# USB_OTG_FS.net
KiCad netlist of a schematic drawn in Altium Designer
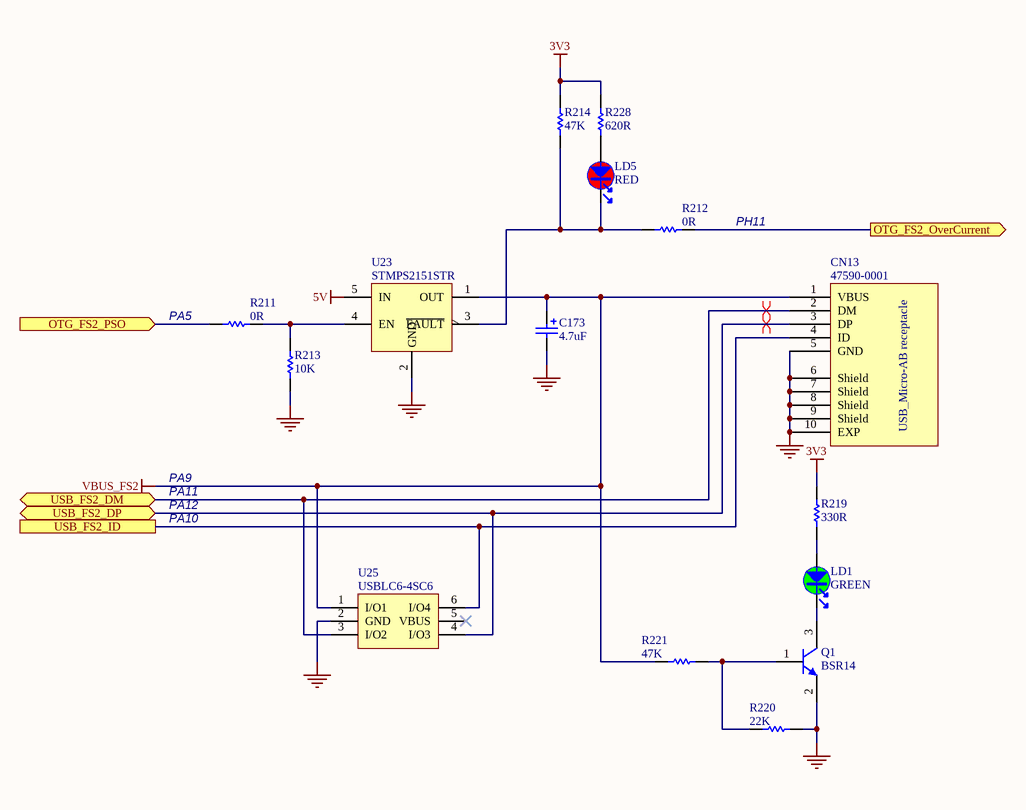
[diagram p0: USB_OTG_FS.SchDoc]

(export (version "E")
  (design (tool "Eeschema 10.0.6"))
  (components
    (comp (ref "C173")
      (value "4.7uF")
      (footprint "CPOL_VISHAY_TANTAL-595D_1407_H220")
      (description "Capacitor, Tantalum, 4.7uF, 16V, +/-10%, 595D case A")
      (fields
        (field (name "INTERNAL_PART_NUMBER") "MCD-00595")
        (field (name "MANUFACTURER_PART_NUMBER") "595D475X9016A2T")
        (field (name "PROVIDED_BY") "Subcon")
      )
      (libsource (lib "MCD_PARTS_database") (part "Cap_POL_TANA"))
    )
    (comp (ref "CN13")
      (value "USB_uAB_47590.0001")
      (footprint "CON_USBMICROAB_MOLEX_47590-0001_H3")
      (description "USB-MICRO-AB, 0.65mm, RA, SMT, Top Mount (compatible with MCD-00661 USB certified)")
      (fields
        (field (name "INTERNAL_PART_NUMBER") "MCD-00022")
        (field (name "MANUFACTURER_PART_NUMBER") "47590-0001")
        (field (name "MANUFACTURER") "MOLEX")
        (field (name "PROVIDED_BY") "Subcon")
      )
      (libsource (lib "MCD_PARTS_database") (part "USB_uAB_47590.0001"))
    )
    (comp (ref "LD1")
      (value "GREEN")
      (footprint "LED_0603_GREEN")
      (description "LED, Green, 2V, 25mA, 0603, SMD")
      (fields (field (name "INTERNAL_PART_NUMBER") "MCD-02900") (field (name "MANUFACTURER") "EVERLIGHT"))
      (libsource (lib "MCD_PARTS_database") (part "LED_green"))
    )
    (comp (ref "LD5")
      (value "RED")
      (footprint "LED_0603_RED")
      (description "LED, Red, VF : Min=1.75V , Max=2.35V, 25mA, 0603")
      (fields (field (name "INTERNAL_PART_NUMBER") "MCD-02899") (field (name "MANUFACTURER") "EVERLIGHT"))
      (libsource (lib "MCD_PARTS_database") (part "LED_red"))
    )
    (comp (ref "Q1")
      (value "BSR14")
      (footprint "NPN_SOT23")
      (description "NPN Bipolar Transistor")
      (fields
        (field (name "INTERNAL_PART_NUMBER") "MCD-00073")
        (field (name "MANUFACTURER") "ON SEMICONDUCTOR")
        (field (name "PROVIDED_BY") "Subcon")
      )
      (libsource (lib "MCD_PARTS_database") (part "9013-SOT23"))
    )
    (comp (ref "R211")
      (value "0R")
      (footprint "R0402")
      (description "Resistor,0R,0402,5%,1/16W")
      (fields
        (field (name "INTERNAL_PART_NUMBER") "MCD-00052")
        (field (name "MANUFACTURER_PART_NUMBER") "RC0402JR-070RL")
        (field (name "PROVIDED_BY") "Subcon")
      )
      (libsource (lib "MCD_PARTS_database") (part "Resistor"))
    )
    (comp (ref "R212")
      (value "0R")
      (footprint "R0402")
      (description "Resistor,0R,0402,5%,1/16W")
      (fields
        (field (name "INTERNAL_PART_NUMBER") "MCD-00052")
        (field (name "MANUFACTURER_PART_NUMBER") "RC0402JR-070RL")
        (field (name "PROVIDED_BY") "Subcon")
      )
      (libsource (lib "MCD_PARTS_database") (part "Resistor"))
    )
    (comp (ref "R213")
      (value "10K")
      (footprint "R0402")
      (description "Resistor,10K,0402,1%,1/16W")
      (fields
        (field (name "INTERNAL_PART_NUMBER") "MCD-00053")
        (field (name "MANUFACTURER_PART_NUMBER") "RC0402FR-0710KL")
        (field (name "PROVIDED_BY") "subcon")
      )
      (libsource (lib "MCD_PARTS_database") (part "Resistor"))
    )
    (comp (ref "R214")
      (value "47K")
      (footprint "R0402")
      (description "Resistor,47K,0402,1%,1/16W")
      (fields
        (field (name "INTERNAL_PART_NUMBER") "MCD-00063")
        (field (name "MANUFACTURER_PART_NUMBER") "RC0402FR-0747KL")
        (field (name "PROVIDED_BY") "Subcon")
      )
      (libsource (lib "MCD_PARTS_database") (part "Resistor"))
    )
    (comp (ref "R219")
      (value "330R")
      (footprint "R0402")
      (description "Resistor,330R,0402,1%,1/16W")
      (fields
        (field (name "INTERNAL_PART_NUMBER") "MCD-00062")
        (field (name "MANUFACTURER_PART_NUMBER") "RC0402FR-07330RL")
        (field (name "PROVIDED_BY") "Subcon")
      )
      (libsource (lib "MCD_PARTS_database") (part "Resistor"))
    )
    (comp (ref "R220")
      (value "22K")
      (footprint "R0402")
      (description "Resistor,22K,0402,1%,1/16W")
      (fields
        (field (name "INTERNAL_PART_NUMBER") "MCD-00429")
        (field (name "MANUFACTURER_PART_NUMBER") "RC0402FR-0722KL")
        (field (name "PROVIDED_BY") "Subcon")
      )
      (libsource (lib "MCD_PARTS_database") (part "Resistor"))
    )
    (comp (ref "R221")
      (value "47K")
      (footprint "R0402")
      (description "Resistor,47K,0402,1%,1/16W")
      (fields
        (field (name "INTERNAL_PART_NUMBER") "MCD-00063")
        (field (name "MANUFACTURER_PART_NUMBER") "RC0402FR-0747KL")
        (field (name "PROVIDED_BY") "Subcon")
      )
      (libsource (lib "MCD_PARTS_database") (part "Resistor"))
    )
    (comp (ref "R228")
      (value "620R")
      (footprint "R0402")
      (description "Resistor,620R,0402,1%,1/16W")
      (fields
        (field (name "INTERNAL_PART_NUMBER") "MCD-00499")
        (field (name "MANUFACTURER_PART_NUMBER") "RC0402FR-07620RL")
        (field (name "PROVIDED_BY") "Subcon")
      )
      (libsource (lib "MCD_PARTS_database") (part "Resistor"))
    )
    (comp (ref "U23")
      (value "STMPS2151STR")
      (footprint "MOS_SOT23-5L")
      (description "500mA, Enhanced single channel power switches with active high enable pin")
      (fields
        (field (name "INTERNAL_PART_NUMBER") "MCD-00159")
        (field (name "MANUFACTURER") "STMICROELECTRONICS")
        (field (name "PROVIDED_BY") "Subcon")
      )
      (libsource (lib "MCD_PARTS_database") (part "STMPS2151STR"))
    )
    (comp (ref "U25")
      (value "USBLC6-4SC6")
      (footprint "ESD_SOT23-6L")
      (description "Very low capacitance ESD protection , 4 lines")
      (fields
        (field (name "INTERNAL_PART_NUMBER") "MCD-00250")
        (field (name "MANUFACTURER") "STMICROELECTRONICS")
        (field (name "PROVIDED_BY") "Subcon")
      )
      (libsource (lib "MCD_PARTS_database") (part "USBLC6-4SC6"))
    )
  )
  (nets
    (net (code "1") (name "/OTG_FS2_OverCurrent") (class "Default")
      (node (ref "R212") (pin "2") (pinfunction "2_2") (pintype "passive"))
    )
    (net (code "2") (name "/OTG_FS2_PSO") (class "Default")
      (node (ref "R211") (pin "1") (pinfunction "1_1") (pintype "passive"))
    )
    (net (code "3") (name "/USB_FS2_DM") (class "Default")
      (node (ref "CN13") (pin "2") (pinfunction "DM_2") (pintype "passive"))
      (node (ref "U25") (pin "3") (pinfunction "I/O2_3") (pintype "passive"))
    )
    (net (code "4") (name "/USB_FS2_DP") (class "Default")
      (node (ref "CN13") (pin "3") (pinfunction "DP_3") (pintype "passive"))
      (node (ref "U25") (pin "4") (pinfunction "I/O3_4") (pintype "passive"))
    )
    (net (code "5") (name "/USB_FS2_ID") (class "Default")
      (node (ref "CN13") (pin "4") (pinfunction "ID_4") (pintype "passive"))
      (node (ref "U25") (pin "6") (pinfunction "I/O4_6") (pintype "passive"))
    )
    (net (code "6") (name "3V3") (class "Default")
      (node (ref "R214") (pin "2") (pinfunction "2_2") (pintype "passive"))
      (node (ref "R219") (pin "2") (pinfunction "2_2") (pintype "passive"))
      (node (ref "R228") (pin "2") (pinfunction "2_2") (pintype "passive"))
    )
    (net (code "7") (name "5V") (class "Default")
      (node (ref "U23") (pin "5") (pinfunction "IN_5") (pintype "passive"))
    )
    (net (code "8") (name "GND") (class "Default")
      (node (ref "C173") (pin "2") (pinfunction "2_2") (pintype "passive"))
      (node (ref "CN13") (pin "10") (pinfunction "EXP_10") (pintype "passive"))
      (node (ref "CN13") (pin "5") (pinfunction "GND_5") (pintype "passive"))
      (node (ref "CN13") (pin "6") (pinfunction "Shield_6") (pintype "passive"))
      (node (ref "CN13") (pin "7") (pinfunction "Shield_7") (pintype "passive"))
      (node (ref "CN13") (pin "8") (pinfunction "Shield_8") (pintype "passive"))
      (node (ref "CN13") (pin "9") (pinfunction "Shield_9") (pintype "passive"))
      (node (ref "Q1") (pin "2") (pinfunction "E_2") (pintype "passive"))
      (node (ref "R213") (pin "1") (pinfunction "1_1") (pintype "passive"))
      (node (ref "R220") (pin "2") (pinfunction "2_2") (pintype "passive"))
      (node (ref "U23") (pin "2") (pinfunction "GND_2") (pintype "passive"))
      (node (ref "U25") (pin "2") (pinfunction "GND_2") (pintype "passive"))
    )
    (net (code "9") (name "Net-(LD1-Pad1)") (class "Default")
      (node (ref "LD1") (pin "1") (pintype "passive"))
      (node (ref "R219") (pin "1") (pinfunction "1_1") (pintype "passive"))
    )
    (net (code "10") (name "Net-(LD5-Pad1)") (class "Default")
      (node (ref "LD5") (pin "1") (pintype "passive"))
      (node (ref "R228") (pin "1") (pinfunction "1_1") (pintype "passive"))
    )
    (net (code "11") (name "Net-(Q1-B)") (class "Default")
      (node (ref "Q1") (pin "1") (pinfunction "B_1") (pintype "passive"))
      (node (ref "R220") (pin "1") (pinfunction "1_1") (pintype "passive"))
      (node (ref "R221") (pin "1") (pinfunction "1_1") (pintype "passive"))
    )
    (net (code "12") (name "Net-(Q1-C)") (class "Default")
      (node (ref "LD1") (pin "2") (pintype "passive"))
      (node (ref "Q1") (pin "3") (pinfunction "C_3") (pintype "passive"))
    )
    (net (code "13") (name "Net-(U23-EN)") (class "Default")
      (node (ref "R211") (pin "2") (pinfunction "2_2") (pintype "passive"))
      (node (ref "R213") (pin "2") (pinfunction "2_2") (pintype "passive"))
      (node (ref "U23") (pin "4") (pinfunction "EN_4") (pintype "passive"))
    )
    (net (code "14") (name "Net-(U23-~{FAULT})") (class "Default")
      (node (ref "LD5") (pin "2") (pintype "passive"))
      (node (ref "R212") (pin "1") (pinfunction "1_1") (pintype "passive"))
      (node (ref "R214") (pin "1") (pinfunction "1_1") (pintype "passive"))
      (node (ref "U23") (pin "3") (pinfunction "~{FAULT}_3") (pintype "passive"))
    )
    (net (code "15") (name "VBUS_FS2") (class "Default")
      (node (ref "C173") (pin "1") (pinfunction "1_1") (pintype "passive"))
      (node (ref "CN13") (pin "1") (pinfunction "VBUS_1") (pintype "passive"))
      (node (ref "R221") (pin "2") (pinfunction "2_2") (pintype "passive"))
      (node (ref "U23") (pin "1") (pinfunction "OUT_1") (pintype "passive"))
      (node (ref "U25") (pin "1") (pinfunction "I/O1_1") (pintype "passive"))
    )
    (net (code "16") (name "unconnected-(U25-VBUS-Pad5)") (class "Default")
      (node (ref "U25") (pin "5") (pinfunction "VBUS_5") (pintype "passive+no_connect"))
    )
  )
)
